# ProPrj_ODO2_2025-07-28.net
KiCad netlist of a schematic drawn in EasyEDA Pro
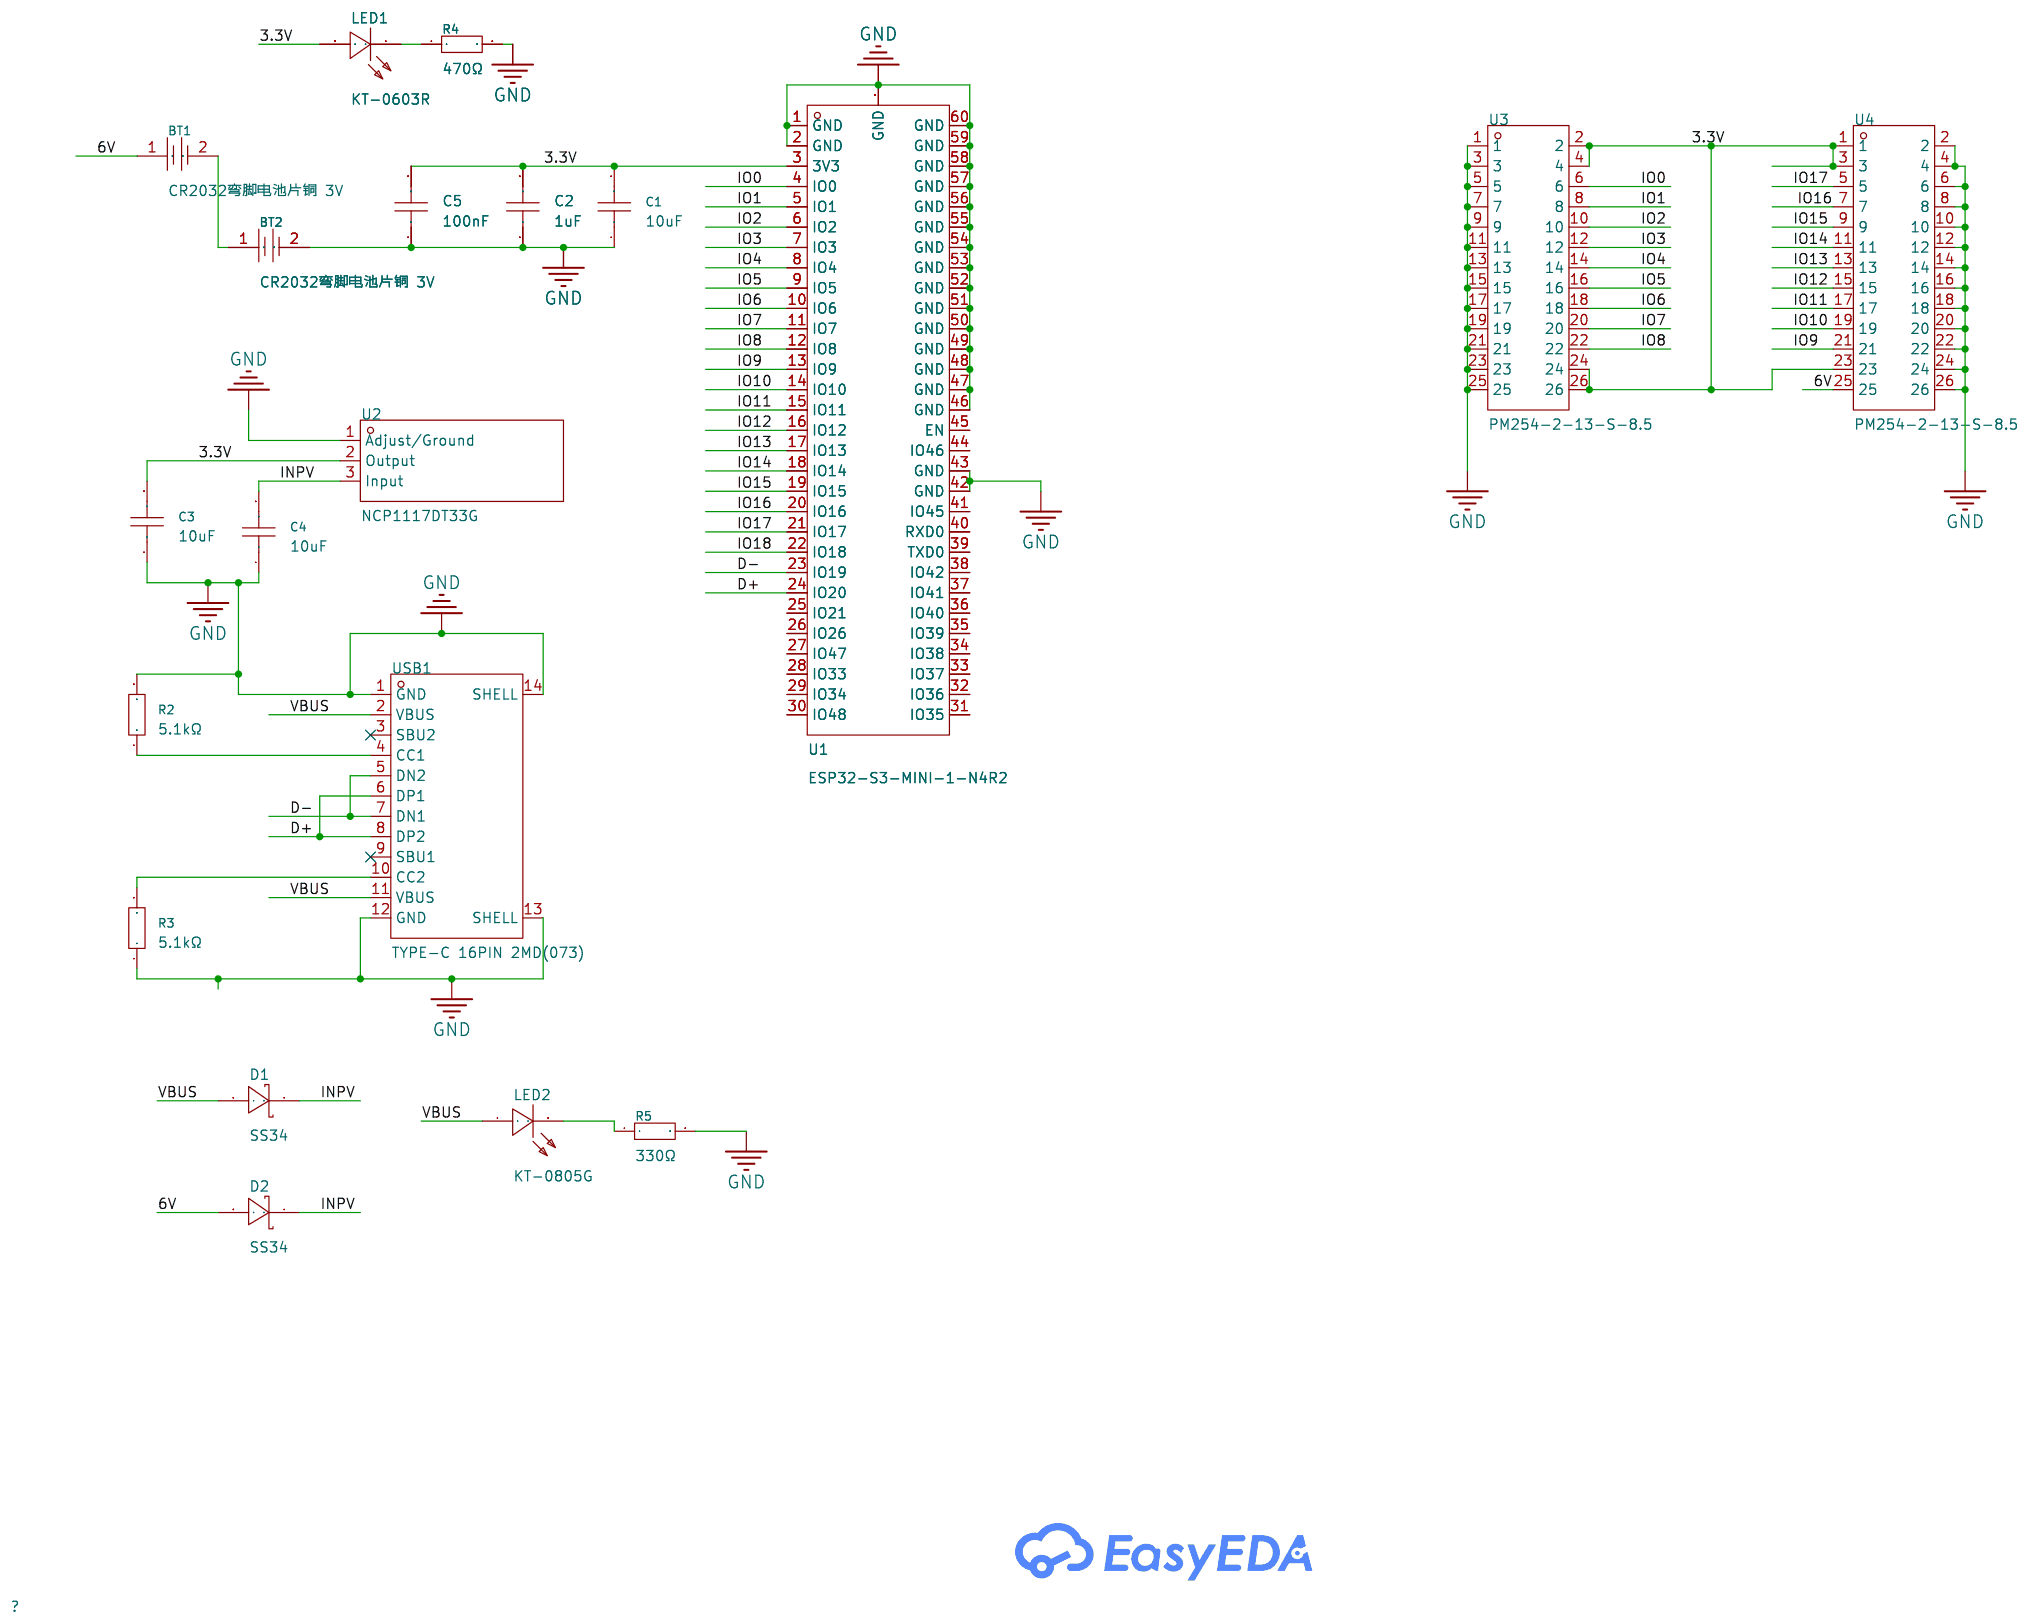
[diagram p0: schematic sheet]

(export (version "E")
  (design (tool "Eeschema 10.0.6"))
  (components
    (comp (ref "BT1")
      (value "CR2032弯脚电池片铜 3V")
      (footprint "easyedapro:BAT-SMD_CR2032-3V")
      (fields (field (name "Manufacturer") "Q&J"))
      (libsource (lib "easyedapro") (part "C70373"))
    )
    (comp (ref "BT2")
      (value "CR2032弯脚电池片铜 3V")
      (footprint "easyedapro:BAT-SMD_CR2032-3V")
      (fields (field (name "Manufacturer") "Q&J"))
      (libsource (lib "easyedapro") (part "C70373"))
    )
    (comp (ref "C1")
      (value "10uF")
      (footprint "easyedapro:C0603")
      (fields
        (field (name "Manufacturer Part") "CL10A106MA8NRNC")
        (field (name "Manufacturer") "SAMSUNG(三星)")
      )
      (libsource (lib "easyedapro") (part "CL10A106MA8NRNC"))
    )
    (comp (ref "C2")
      (value "1uF")
      (footprint "easyedapro:C0603")
      (fields
        (field (name "Manufacturer Part") "CL10A105KB8NNNC")
        (field (name "Manufacturer") "SAMSUNG(三星)")
      )
      (libsource (lib "easyedapro") (part "CL10A105KB8NNNC"))
    )
    (comp (ref "C3")
      (value "10uF")
      (footprint "easyedapro:C0603")
      (fields
        (field (name "Manufacturer Part") "CL10A106MA8NRNC")
        (field (name "Manufacturer") "SAMSUNG(三星)")
      )
      (libsource (lib "easyedapro") (part "CL10A106MA8NRNC"))
    )
    (comp (ref "C4")
      (value "10uF")
      (footprint "easyedapro:C0603")
      (fields
        (field (name "Manufacturer Part") "CL10A106MA8NRNC")
        (field (name "Manufacturer") "SAMSUNG(三星)")
      )
      (libsource (lib "easyedapro") (part "CL10A106MA8NRNC"))
    )
    (comp (ref "C5")
      (value "100nF")
      (footprint "easyedapro:C0402")
      (fields
        (field (name "Manufacturer Part") "CL05B104KO5NNNC")
        (field (name "Manufacturer") "SAMSUNG(三星)")
      )
      (libsource (lib "easyedapro") (part "CL05B104KO5NNNC"))
    )
    (comp (ref "D1")
      (value "SS34")
      (footprint "easyedapro:SMA_L4.3-W2.6-LS5.2-RD")
      (fields (field (name "Manufacturer") "MDD(辰达半导体)"))
      (libsource (lib "easyedapro") (part "SS34_C8678"))
    )
    (comp (ref "D2")
      (value "SS34")
      (footprint "easyedapro:SMA_L4.3-W2.6-LS5.2-RD")
      (fields (field (name "Manufacturer") "MDD(辰达半导体)"))
      (libsource (lib "easyedapro") (part "SS34_C8678"))
    )
    (comp (ref "LED1")
      (value "KT-0603R")
      (footprint "easyedapro:LED0603-RD")
      (fields (field (name "Manufacturer") "KENTO"))
      (libsource (lib "easyedapro") (part "KT-0603R"))
    )
    (comp (ref "LED2")
      (value "KT-0805G")
      (footprint "easyedapro:LED0805-R-RD")
      (fields (field (name "Manufacturer") "KENTO"))
      (libsource (lib "easyedapro") (part "0805G (Green)"))
    )
    (comp (ref "R2")
      (value "5.1kΩ")
      (footprint "easyedapro:R0402")
      (fields
        (field (name "Manufacturer Part") "0402WGF5101TCE")
        (field (name "Manufacturer") "UNI-ROYAL(厚声)")
      )
      (libsource (lib "easyedapro") (part "0402WGF5101TCE"))
    )
    (comp (ref "R3")
      (value "5.1kΩ")
      (footprint "easyedapro:R0402")
      (fields
        (field (name "Manufacturer Part") "0402WGF5101TCE")
        (field (name "Manufacturer") "UNI-ROYAL(厚声)")
      )
      (libsource (lib "easyedapro") (part "0402WGF5101TCE"))
    )
    (comp (ref "R4")
      (value "470Ω")
      (footprint "easyedapro:R0805")
      (fields
        (field (name "Manufacturer Part") "0805W8F4700T5E")
        (field (name "Manufacturer") "UNI-ROYAL(厚声)")
      )
      (libsource (lib "easyedapro") (part "0805W8F4700T5E"))
    )
    (comp (ref "R5")
      (value "330Ω")
      (footprint "easyedapro:R0805")
      (fields
        (field (name "Manufacturer Part") "0805W8F3300T5E")
        (field (name "Manufacturer") "UNI-ROYAL(厚声)")
      )
      (libsource (lib "easyedapro") (part "0805W8F3300T5E"))
    )
    (comp (ref "U1")
      (value "ESP32-S3-MINI-1-N4R2")
      (footprint "easyedapro:BULETM-SMD_ESP32-S3-MINI-1-N8")
      (description "Antenna Type:On-Board PCB Antenna")
      (fields (field (name "Manufacturer") "ESPRESSIF(乐鑫)"))
      (libsource (lib "easyedapro") (part "ESP32-S3-MINI-1-N4R2"))
    )
    (comp (ref "U2")
      (value "NCP1117DT33G")
      (footprint "easyedapro:TO-252_L6.5-W6.1-P4.58-LS9.9-BR")
      (fields (field (name "Manufacturer") "onsemi(安森美)"))
      (libsource (lib "easyedapro") (part "NCP1117DT33G"))
    )
    (comp (ref "U3")
      (value "PM254-2-13-S-8.5")
      (footprint "easyedapro:HDR-SMD_26P-P2.54-V-F-R2-C13-LS7.2")
      (fields (field (name "Manufacturer") "HCTL(华灿天禄)"))
      (libsource (lib "easyedapro") (part "PM254-2-13-S-8.5"))
    )
    (comp (ref "U4")
      (value "PM254-2-13-S-8.5")
      (footprint "easyedapro:HDR-SMD_26P-P2.54-V-F-R2-C13-LS7.2")
      (fields (field (name "Manufacturer") "HCTL(华灿天禄)"))
      (libsource (lib "easyedapro") (part "PM254-2-13-S-8.5"))
    )
    (comp (ref "USB1")
      (value "TYPE-C 16PIN 2MD(073)")
      (footprint "easyedapro:USB-C-SMD_TYPE-C-6PIN-2MD-073")
      (fields (field (name "Manufacturer") "SHOU HAN(首韩)"))
      (libsource (lib "easyedapro") (part "TYPE-C 16PIN 2MD(073)"))
    )
  )
  (nets
    (net (code "1") (name "/3.3V") (class "Default")
      (node (ref "C1") (pin "2") (pinfunction "2_2") (pintype "input"))
      (node (ref "C2") (pin "2") (pinfunction "2_2") (pintype "unspecified"))
      (node (ref "C3") (pin "2") (pinfunction "2_2") (pintype "input"))
      (node (ref "C5") (pin "2") (pinfunction "2_2") (pintype "unspecified"))
      (node (ref "LED1") (pin "2") (pinfunction "A_2") (pintype "unspecified"))
      (node (ref "U1") (pin "3") (pinfunction "3V3_3") (pintype "unspecified"))
      (node (ref "U2") (pin "2") (pinfunction "Output_2") (pintype "unspecified"))
      (node (ref "U3") (pin "2") (pinfunction "2_2") (pintype "unspecified"))
      (node (ref "U3") (pin "24") (pinfunction "24_24") (pintype "unspecified"))
      (node (ref "U3") (pin "26") (pinfunction "26_26") (pintype "unspecified"))
      (node (ref "U3") (pin "4") (pinfunction "4_4") (pintype "unspecified"))
      (node (ref "U4") (pin "1") (pinfunction "1_1") (pintype "unspecified"))
      (node (ref "U4") (pin "23") (pinfunction "23_23") (pintype "unspecified"))
      (node (ref "U4") (pin "3") (pinfunction "3_3") (pintype "unspecified"))
    )
    (net (code "2") (name "/6V") (class "Default")
      (node (ref "BT1") (pin "1") (pinfunction "1_1") (pintype "input"))
      (node (ref "D2") (pin "2") (pinfunction "A_2") (pintype "unspecified"))
      (node (ref "U4") (pin "25") (pinfunction "25_25") (pintype "unspecified"))
    )
    (net (code "3") (name "/D+") (class "Default")
      (node (ref "U1") (pin "24") (pinfunction "IO20_24") (pintype "unspecified"))
      (node (ref "USB1") (pin "6") (pinfunction "DP1_6") (pintype "unspecified"))
      (node (ref "USB1") (pin "8") (pinfunction "DP2_8") (pintype "unspecified"))
    )
    (net (code "4") (name "/D-") (class "Default")
      (node (ref "U1") (pin "23") (pinfunction "IO19_23") (pintype "unspecified"))
      (node (ref "USB1") (pin "5") (pinfunction "DN2_5") (pintype "unspecified"))
      (node (ref "USB1") (pin "7") (pinfunction "DN1_7") (pintype "unspecified"))
    )
    (net (code "5") (name "/INPV") (class "Default")
      (node (ref "C4") (pin "2") (pinfunction "2_2") (pintype "input"))
      (node (ref "D1") (pin "1") (pinfunction "K_1") (pintype "unspecified"))
      (node (ref "D2") (pin "1") (pinfunction "K_1") (pintype "unspecified"))
      (node (ref "U2") (pin "3") (pinfunction "Input_3") (pintype "unspecified"))
    )
    (net (code "6") (name "/IO0") (class "Default")
      (node (ref "U1") (pin "4") (pinfunction "IO0_4") (pintype "unspecified"))
      (node (ref "U3") (pin "6") (pinfunction "6_6") (pintype "unspecified"))
    )
    (net (code "7") (name "/IO1") (class "Default")
      (node (ref "U1") (pin "5") (pinfunction "IO1_5") (pintype "unspecified"))
      (node (ref "U3") (pin "8") (pinfunction "8_8") (pintype "unspecified"))
    )
    (net (code "8") (name "/IO2") (class "Default")
      (node (ref "U1") (pin "6") (pinfunction "IO2_6") (pintype "unspecified"))
      (node (ref "U3") (pin "10") (pinfunction "10_10") (pintype "unspecified"))
    )
    (net (code "9") (name "/IO3") (class "Default")
      (node (ref "U1") (pin "7") (pinfunction "IO3_7") (pintype "unspecified"))
      (node (ref "U3") (pin "12") (pinfunction "12_12") (pintype "unspecified"))
    )
    (net (code "10") (name "/IO4") (class "Default")
      (node (ref "U1") (pin "8") (pinfunction "IO4_8") (pintype "unspecified"))
      (node (ref "U3") (pin "14") (pinfunction "14_14") (pintype "unspecified"))
    )
    (net (code "11") (name "/IO5") (class "Default")
      (node (ref "U1") (pin "9") (pinfunction "IO5_9") (pintype "unspecified"))
      (node (ref "U3") (pin "16") (pinfunction "16_16") (pintype "unspecified"))
    )
    (net (code "12") (name "/IO6") (class "Default")
      (node (ref "U1") (pin "10") (pinfunction "IO6_10") (pintype "unspecified"))
      (node (ref "U3") (pin "18") (pinfunction "18_18") (pintype "unspecified"))
    )
    (net (code "13") (name "/IO7") (class "Default")
      (node (ref "U1") (pin "11") (pinfunction "IO7_11") (pintype "unspecified"))
      (node (ref "U3") (pin "20") (pinfunction "20_20") (pintype "unspecified"))
    )
    (net (code "14") (name "/IO8") (class "Default")
      (node (ref "U1") (pin "12") (pinfunction "IO8_12") (pintype "unspecified"))
      (node (ref "U3") (pin "22") (pinfunction "22_22") (pintype "unspecified"))
    )
    (net (code "15") (name "/IO9") (class "Default")
      (node (ref "U1") (pin "13") (pinfunction "IO9_13") (pintype "unspecified"))
      (node (ref "U4") (pin "21") (pinfunction "21_21") (pintype "unspecified"))
    )
    (net (code "16") (name "/IO10") (class "Default")
      (node (ref "U1") (pin "14") (pinfunction "IO10_14") (pintype "unspecified"))
      (node (ref "U4") (pin "19") (pinfunction "19_19") (pintype "unspecified"))
    )
    (net (code "17") (name "/IO11") (class "Default")
      (node (ref "U1") (pin "15") (pinfunction "IO11_15") (pintype "unspecified"))
      (node (ref "U4") (pin "17") (pinfunction "17_17") (pintype "unspecified"))
    )
    (net (code "18") (name "/IO12") (class "Default")
      (node (ref "U1") (pin "16") (pinfunction "IO12_16") (pintype "unspecified"))
      (node (ref "U4") (pin "15") (pinfunction "15_15") (pintype "unspecified"))
    )
    (net (code "19") (name "/IO13") (class "Default")
      (node (ref "U1") (pin "17") (pinfunction "IO13_17") (pintype "unspecified"))
      (node (ref "U4") (pin "13") (pinfunction "13_13") (pintype "unspecified"))
    )
    (net (code "20") (name "/IO14") (class "Default")
      (node (ref "U1") (pin "18") (pinfunction "IO14_18") (pintype "unspecified"))
      (node (ref "U4") (pin "11") (pinfunction "11_11") (pintype "unspecified"))
    )
    (net (code "21") (name "/IO15") (class "Default")
      (node (ref "U1") (pin "19") (pinfunction "IO15_19") (pintype "unspecified"))
      (node (ref "U4") (pin "9") (pinfunction "9_9") (pintype "unspecified"))
    )
    (net (code "22") (name "/IO16") (class "Default")
      (node (ref "U1") (pin "20") (pinfunction "IO16_20") (pintype "unspecified"))
      (node (ref "U4") (pin "7") (pinfunction "7_7") (pintype "unspecified"))
    )
    (net (code "23") (name "/IO17") (class "Default")
      (node (ref "U1") (pin "21") (pinfunction "IO17_21") (pintype "unspecified"))
      (node (ref "U4") (pin "5") (pinfunction "5_5") (pintype "unspecified"))
    )
    (net (code "24") (name "/IO18") (class "Default")
      (node (ref "U1") (pin "22") (pinfunction "IO18_22") (pintype "unspecified"))
    )
    (net (code "25") (name "/VBUS") (class "Default")
      (node (ref "D1") (pin "2") (pinfunction "A_2") (pintype "unspecified"))
      (node (ref "LED2") (pin "1") (pinfunction "A_1") (pintype "unspecified"))
      (node (ref "USB1") (pin "11") (pinfunction "VBUS_11") (pintype "unspecified"))
      (node (ref "USB1") (pin "2") (pinfunction "VBUS_2") (pintype "unspecified"))
    )
    (net (code "26") (name "GND") (class "Default")
      (node (ref "BT2") (pin "2") (pinfunction "2_2") (pintype "input"))
      (node (ref "C1") (pin "1") (pinfunction "1_1") (pintype "input"))
      (node (ref "C2") (pin "1") (pinfunction "1_1") (pintype "unspecified"))
      (node (ref "C3") (pin "1") (pinfunction "1_1") (pintype "input"))
      (node (ref "C4") (pin "1") (pinfunction "1_1") (pintype "input"))
      (node (ref "C5") (pin "1") (pinfunction "1_1") (pintype "unspecified"))
      (node (ref "R2") (pin "2") (pinfunction "2_2") (pintype "input"))
      (node (ref "R3") (pin "1") (pinfunction "1_1") (pintype "input"))
      (node (ref "R4") (pin "2") (pinfunction "2_2") (pintype "input"))
      (node (ref "R5") (pin "2") (pinfunction "2_2") (pintype "input"))
      (node (ref "U1") (pin "1") (pinfunction "GND_1") (pintype "unspecified"))
      (node (ref "U1") (pin "2") (pinfunction "GND_2") (pintype "unspecified"))
      (node (ref "U1") (pin "42") (pinfunction "GND_42") (pintype "unspecified"))
      (node (ref "U1") (pin "43") (pinfunction "GND_43") (pintype "unspecified"))
      (node (ref "U1") (pin "46") (pinfunction "GND_46") (pintype "unspecified"))
      (node (ref "U1") (pin "47") (pinfunction "GND_47") (pintype "unspecified"))
      (node (ref "U1") (pin "48") (pinfunction "GND_48") (pintype "unspecified"))
      (node (ref "U1") (pin "49") (pinfunction "GND_49") (pintype "unspecified"))
      (node (ref "U1") (pin "50") (pinfunction "GND_50") (pintype "unspecified"))
      (node (ref "U1") (pin "51") (pinfunction "GND_51") (pintype "unspecified"))
      (node (ref "U1") (pin "52") (pinfunction "GND_52") (pintype "unspecified"))
      (node (ref "U1") (pin "53") (pinfunction "GND_53") (pintype "unspecified"))
      (node (ref "U1") (pin "54") (pinfunction "GND_54") (pintype "unspecified"))
      (node (ref "U1") (pin "55") (pinfunction "GND_55") (pintype "unspecified"))
      (node (ref "U1") (pin "56") (pinfunction "GND_56") (pintype "unspecified"))
      (node (ref "U1") (pin "57") (pinfunction "GND_57") (pintype "unspecified"))
      (node (ref "U1") (pin "58") (pinfunction "GND_58") (pintype "unspecified"))
      (node (ref "U1") (pin "59") (pinfunction "GND_59") (pintype "unspecified"))
      (node (ref "U1") (pin "60") (pinfunction "GND_60") (pintype "unspecified"))
      (node (ref "U1") (pin "GND") (pinfunction "GND_GND") (pintype "unspecified"))
      (node (ref "U2") (pin "1") (pinfunction "Adjust/Ground_1") (pintype "unspecified"))
      (node (ref "U3") (pin "1") (pinfunction "1_1") (pintype "unspecified"))
      (node (ref "U3") (pin "11") (pinfunction "11_11") (pintype "unspecified"))
      (node (ref "U3") (pin "13") (pinfunction "13_13") (pintype "unspecified"))
      (node (ref "U3") (pin "15") (pinfunction "15_15") (pintype "unspecified"))
      (node (ref "U3") (pin "17") (pinfunction "17_17") (pintype "unspecified"))
      (node (ref "U3") (pin "19") (pinfunction "19_19") (pintype "unspecified"))
      (node (ref "U3") (pin "21") (pinfunction "21_21") (pintype "unspecified"))
      (node (ref "U3") (pin "23") (pinfunction "23_23") (pintype "unspecified"))
      (node (ref "U3") (pin "25") (pinfunction "25_25") (pintype "unspecified"))
      (node (ref "U3") (pin "3") (pinfunction "3_3") (pintype "unspecified"))
      (node (ref "U3") (pin "5") (pinfunction "5_5") (pintype "unspecified"))
      (node (ref "U3") (pin "7") (pinfunction "7_7") (pintype "unspecified"))
      (node (ref "U3") (pin "9") (pinfunction "9_9") (pintype "unspecified"))
      (node (ref "U4") (pin "10") (pinfunction "10_10") (pintype "unspecified"))
      (node (ref "U4") (pin "12") (pinfunction "12_12") (pintype "unspecified"))
      (node (ref "U4") (pin "14") (pinfunction "14_14") (pintype "unspecified"))
      (node (ref "U4") (pin "16") (pinfunction "16_16") (pintype "unspecified"))
      (node (ref "U4") (pin "18") (pinfunction "18_18") (pintype "unspecified"))
      (node (ref "U4") (pin "2") (pinfunction "2_2") (pintype "unspecified"))
      (node (ref "U4") (pin "20") (pinfunction "20_20") (pintype "unspecified"))
      (node (ref "U4") (pin "22") (pinfunction "22_22") (pintype "unspecified"))
      (node (ref "U4") (pin "24") (pinfunction "24_24") (pintype "unspecified"))
      (node (ref "U4") (pin "26") (pinfunction "26_26") (pintype "unspecified"))
      (node (ref "U4") (pin "4") (pinfunction "4_4") (pintype "unspecified"))
      (node (ref "U4") (pin "6") (pinfunction "6_6") (pintype "unspecified"))
      (node (ref "U4") (pin "8") (pinfunction "8_8") (pintype "unspecified"))
      (node (ref "USB1") (pin "1") (pinfunction "GND_1") (pintype "unspecified"))
      (node (ref "USB1") (pin "12") (pinfunction "GND_12") (pintype "unspecified"))
      (node (ref "USB1") (pin "13") (pinfunction "SHELL_13") (pintype "unspecified"))
      (node (ref "USB1") (pin "14") (pinfunction "SHELL_14") (pintype "unspecified"))
    )
    (net (code "27") (name "Net-(BT1-Pad2)") (class "Default")
      (node (ref "BT1") (pin "2") (pinfunction "2_2") (pintype "input"))
      (node (ref "BT2") (pin "1") (pinfunction "1_1") (pintype "input"))
    )
    (net (code "28") (name "Net-(LED1-K)") (class "Default")
      (node (ref "LED1") (pin "1") (pinfunction "K_1") (pintype "unspecified"))
      (node (ref "R4") (pin "1") (pinfunction "1_1") (pintype "input"))
    )
    (net (code "29") (name "Net-(LED2-K)") (class "Default")
      (node (ref "LED2") (pin "2") (pinfunction "K_2") (pintype "unspecified"))
      (node (ref "R5") (pin "1") (pinfunction "1_1") (pintype "input"))
    )
    (net (code "30") (name "Net-(USB1-CC1)") (class "Default")
      (node (ref "R2") (pin "1") (pinfunction "1_1") (pintype "input"))
      (node (ref "USB1") (pin "4") (pinfunction "CC1_4") (pintype "unspecified"))
    )
    (net (code "31") (name "Net-(USB1-CC2)") (class "Default")
      (node (ref "R3") (pin "2") (pinfunction "2_2") (pintype "input"))
      (node (ref "USB1") (pin "10") (pinfunction "CC2_10") (pintype "unspecified"))
    )
    (net (code "32") (name "unconnected-(U1-EN-Pad45)") (class "Default")
      (node (ref "U1") (pin "45") (pinfunction "EN_45") (pintype "unspecified"))
    )
    (net (code "33") (name "unconnected-(U1-IO21-Pad25)") (class "Default")
      (node (ref "U1") (pin "25") (pinfunction "IO21_25") (pintype "unspecified"))
    )
    (net (code "34") (name "unconnected-(U1-IO26-Pad26)") (class "Default")
      (node (ref "U1") (pin "26") (pinfunction "IO26_26") (pintype "unspecified"))
    )
    (net (code "35") (name "unconnected-(U1-IO33-Pad28)") (class "Default")
      (node (ref "U1") (pin "28") (pinfunction "IO33_28") (pintype "unspecified"))
    )
    (net (code "36") (name "unconnected-(U1-IO34-Pad29)") (class "Default")
      (node (ref "U1") (pin "29") (pinfunction "IO34_29") (pintype "unspecified"))
    )
    (net (code "37") (name "unconnected-(U1-IO35-Pad31)") (class "Default")
      (node (ref "U1") (pin "31") (pinfunction "IO35_31") (pintype "unspecified"))
    )
    (net (code "38") (name "unconnected-(U1-IO36-Pad32)") (class "Default")
      (node (ref "U1") (pin "32") (pinfunction "IO36_32") (pintype "unspecified"))
    )
    (net (code "39") (name "unconnected-(U1-IO37-Pad33)") (class "Default")
      (node (ref "U1") (pin "33") (pinfunction "IO37_33") (pintype "unspecified"))
    )
    (net (code "40") (name "unconnected-(U1-IO38-Pad34)") (class "Default")
      (node (ref "U1") (pin "34") (pinfunction "IO38_34") (pintype "unspecified"))
    )
    (net (code "41") (name "unconnected-(U1-IO39-Pad35)") (class "Default")
      (node (ref "U1") (pin "35") (pinfunction "IO39_35") (pintype "unspecified"))
    )
    (net (code "42") (name "unconnected-(U1-IO40-Pad36)") (class "Default")
      (node (ref "U1") (pin "36") (pinfunction "IO40_36") (pintype "unspecified"))
    )
    (net (code "43") (name "unconnected-(U1-IO41-Pad37)") (class "Default")
      (node (ref "U1") (pin "37") (pinfunction "IO41_37") (pintype "unspecified"))
    )
    (net (code "44") (name "unconnected-(U1-IO42-Pad38)") (class "Default")
      (node (ref "U1") (pin "38") (pinfunction "IO42_38") (pintype "unspecified"))
    )
    (net (code "45") (name "unconnected-(U1-IO45-Pad41)") (class "Default")
      (node (ref "U1") (pin "41") (pinfunction "IO45_41") (pintype "unspecified"))
    )
    (net (code "46") (name "unconnected-(U1-IO46-Pad44)") (class "Default")
      (node (ref "U1") (pin "44") (pinfunction "IO46_44") (pintype "unspecified"))
    )
    (net (code "47") (name "unconnected-(U1-IO47-Pad27)") (class "Default")
      (node (ref "U1") (pin "27") (pinfunction "IO47_27") (pintype "unspecified"))
    )
    (net (code "48") (name "unconnected-(U1-IO48-Pad30)") (class "Default")
      (node (ref "U1") (pin "30") (pinfunction "IO48_30") (pintype "unspecified"))
    )
    (net (code "49") (name "unconnected-(U1-RXD0-Pad40)") (class "Default")
      (node (ref "U1") (pin "40") (pinfunction "RXD0_40") (pintype "unspecified"))
    )
    (net (code "50") (name "unconnected-(U1-TXD0-Pad39)") (class "Default")
      (node (ref "U1") (pin "39") (pinfunction "TXD0_39") (pintype "unspecified"))
    )
    (net (code "51") (name "unconnected-(USB1-SBU1-Pad9)") (class "Default")
      (node (ref "USB1") (pin "9") (pinfunction "SBU1_9") (pintype "unspecified+no_connect"))
    )
    (net (code "52") (name "unconnected-(USB1-SBU2-Pad3)") (class "Default")
      (node (ref "USB1") (pin "3") (pinfunction "SBU2_3") (pintype "unspecified+no_connect"))
    )
  )
)
